# algyan_8th_es.net
KiCad netlist of a schematic drawn in EAGLE
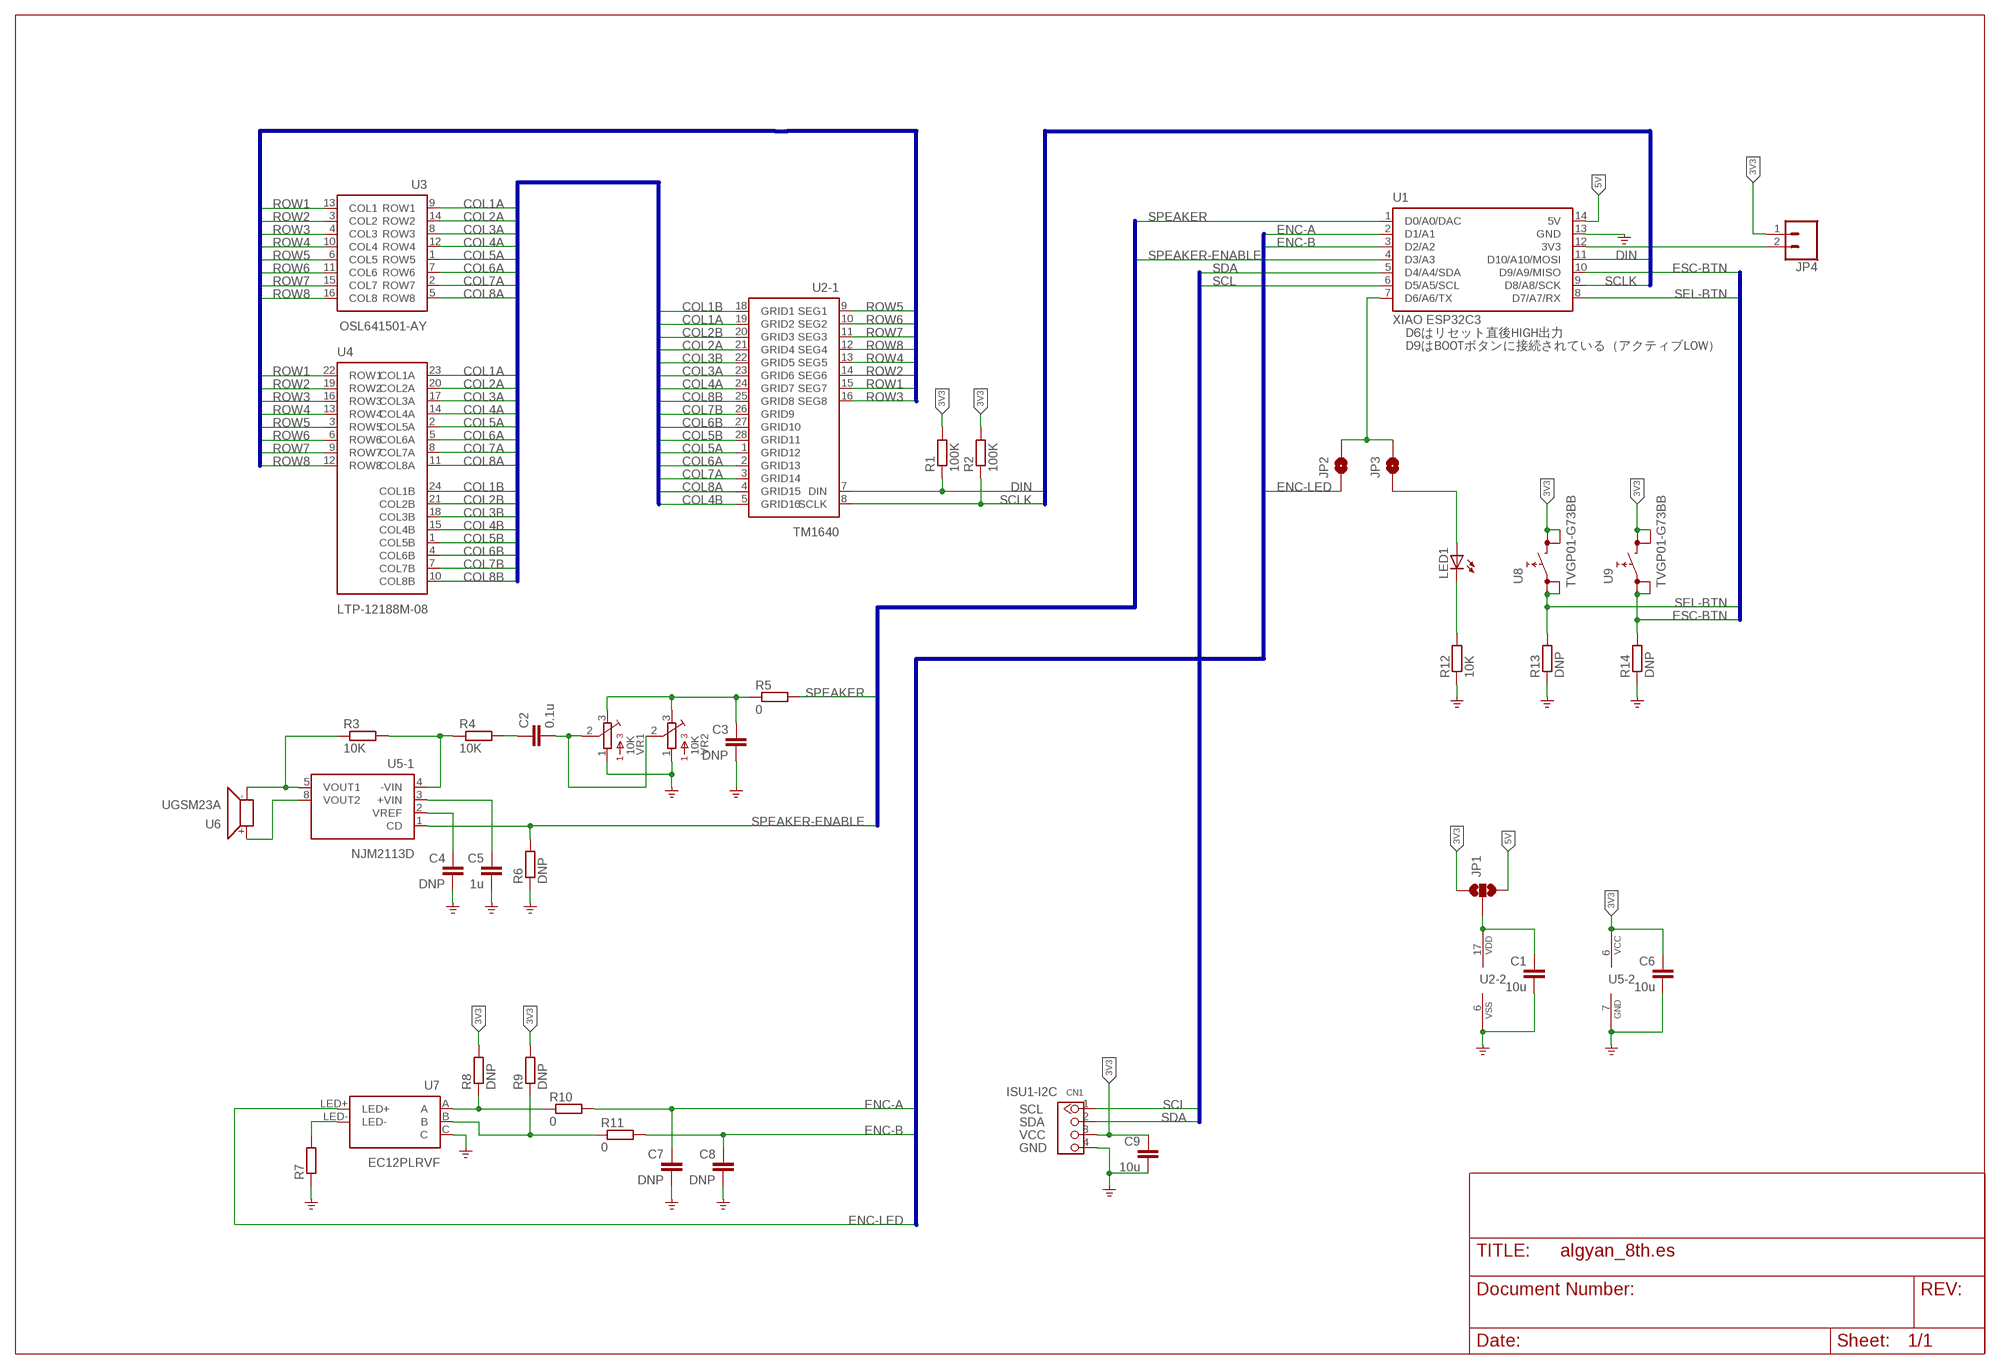
[diagram p0: schematic, sheet 1]

(export (version "E")
  (design (tool "Eeschema 10.0.6"))
  (components
    (comp (ref "C1")
      (value "10u")
      (footprint "eagle-import:C0805")
      (libsource (lib "eagle-import") (part "C-EUC0805"))
    )
    (comp (ref "C2")
      (value "0.1u")
      (footprint "eagle-import:C0603")
      (libsource (lib "eagle-import") (part "C-EUC0603"))
    )
    (comp (ref "C3")
      (value "DNP")
      (footprint "eagle-import:C0805")
      (libsource (lib "eagle-import") (part "C-EUC0805"))
    )
    (comp (ref "C4")
      (value "DNP")
      (footprint "eagle-import:C0805")
      (libsource (lib "eagle-import") (part "C-EUC0805"))
    )
    (comp (ref "C5")
      (value "1u")
      (footprint "eagle-import:C0805")
      (libsource (lib "eagle-import") (part "C-EUC0805"))
    )
    (comp (ref "C6")
      (value "10u")
      (footprint "eagle-import:C0805")
      (libsource (lib "eagle-import") (part "C-EUC0805"))
    )
    (comp (ref "C7")
      (value "DNP")
      (footprint "eagle-import:C0603")
      (libsource (lib "eagle-import") (part "C-EUC0603"))
    )
    (comp (ref "C8")
      (value "DNP")
      (footprint "eagle-import:C0603")
      (libsource (lib "eagle-import") (part "C-EUC0603"))
    )
    (comp (ref "C9")
      (value "10u")
      (footprint "eagle-import:C0805")
      (libsource (lib "eagle-import") (part "C-EUC0805"))
    )
    (comp (ref "CN1")
      (value "4P-2.0")
      (footprint "eagle-import:HW4-2.0")
      (libsource (lib "eagle-import") (part "GROVE-CONNECTOR-DIP(4P-2.0)"))
    )
    (comp (ref "JP1")
      (value "JUMPER-SMT_3_NO_SILK")
      (footprint "eagle-import:SMT-JUMPER_3_NO_SILK")
      (libsource (lib "eagle-import") (part "JUMPER-SMT_3_NO_SILK"))
    )
    (comp (ref "JP2")
      (value "JUMPER-SMT_2_NO_SILK")
      (footprint "eagle-import:SMT-JUMPER_2_NO_SILK")
      (libsource (lib "eagle-import") (part "JUMPER-SMT_2_NO_SILK"))
    )
    (comp (ref "JP3")
      (value "JUMPER-SMT_2_NO_SILK")
      (footprint "eagle-import:SMT-JUMPER_2_NO_SILK")
      (libsource (lib "eagle-import") (part "JUMPER-SMT_2_NO_SILK"))
    )
    (comp (ref "JP4")
      (value "CONN_02")
      (footprint "eagle-import:1X02")
      (libsource (lib "eagle-import") (part "CONN_02"))
    )
    (comp (ref "LED1")
      (value "LED5MM")
      (footprint "eagle-import:LED5MM")
      (libsource (lib "eagle-import") (part "LED5MM"))
    )
    (comp (ref "R1")
      (value "100K")
      (footprint "eagle-import:R0603")
      (libsource (lib "eagle-import") (part "R-EU_R0603"))
    )
    (comp (ref "R2")
      (value "100K")
      (footprint "eagle-import:R0603")
      (libsource (lib "eagle-import") (part "R-EU_R0603"))
    )
    (comp (ref "R3")
      (value "10K")
      (footprint "eagle-import:R0603")
      (libsource (lib "eagle-import") (part "R-EU_R0603"))
    )
    (comp (ref "R4")
      (value "10K")
      (footprint "eagle-import:R0603")
      (libsource (lib "eagle-import") (part "R-EU_R0603"))
    )
    (comp (ref "R5")
      (value "0")
      (footprint "eagle-import:R0603")
      (libsource (lib "eagle-import") (part "R-EU_R0603"))
    )
    (comp (ref "R6")
      (value "DNP")
      (footprint "eagle-import:R0603")
      (libsource (lib "eagle-import") (part "R-EU_R0603"))
    )
    (comp (ref "R7")
      (value "R-EU_R0603")
      (footprint "eagle-import:R0603")
      (libsource (lib "eagle-import") (part "R-EU_R0603"))
    )
    (comp (ref "R8")
      (value "DNP")
      (footprint "eagle-import:R0603")
      (libsource (lib "eagle-import") (part "R-EU_R0603"))
    )
    (comp (ref "R9")
      (value "DNP")
      (footprint "eagle-import:R0603")
      (libsource (lib "eagle-import") (part "R-EU_R0603"))
    )
    (comp (ref "R10")
      (value "0")
      (footprint "eagle-import:R0603")
      (libsource (lib "eagle-import") (part "R-EU_R0603"))
    )
    (comp (ref "R11")
      (value "0")
      (footprint "eagle-import:R0603")
      (libsource (lib "eagle-import") (part "R-EU_R0603"))
    )
    (comp (ref "R12")
      (value "10K")
      (footprint "eagle-import:R0603")
      (libsource (lib "eagle-import") (part "R-EU_R0603"))
    )
    (comp (ref "R13")
      (value "DNP")
      (footprint "eagle-import:R0603")
      (libsource (lib "eagle-import") (part "R-EU_R0603"))
    )
    (comp (ref "R14")
      (value "DNP")
      (footprint "eagle-import:R0603")
      (libsource (lib "eagle-import") (part "R-EU_R0603"))
    )
    (comp (ref "U1")
      (value "XIAO ESP32C3")
      (footprint "eagle-import:SEEEDUINOXIAO")
      (libsource (lib "eagle-import") (part "SEEEDUINOXIAO"))
    )
    (comp (ref "U2")
      (value "TM1640")
      (footprint "eagle-import:TM1640")
      (libsource (lib "eagle-import") (part "TM1640"))
    )
    (comp (ref "U3")
      (value "OSL641501-AY")
      (footprint "eagle-import:OSL641501")
      (libsource (lib "eagle-import") (part "OSL641501-AY"))
    )
    (comp (ref "U4")
      (value "LTP-12188M-08")
      (footprint "eagle-import:LTP-12188M")
      (libsource (lib "eagle-import") (part "LTP-12188M-08"))
    )
    (comp (ref "U5")
      (value "NJM2113D")
      (footprint "eagle-import:DIL08")
      (libsource (lib "eagle-import") (part "NJM2113D"))
    )
    (comp (ref "U6")
      (value "UGSM23A")
      (footprint "eagle-import:UGSM23A")
      (libsource (lib "eagle-import") (part "UGSM23A"))
    )
    (comp (ref "U7")
      (value "EC12PLRVF")
      (footprint "eagle-import:EC12PLRVF")
      (libsource (lib "eagle-import") (part "EC12PLVFR"))
    )
    (comp (ref "U8")
      (value "TVGP01-G73BB")
      (footprint "eagle-import:TVGP01-G73BB")
      (libsource (lib "eagle-import") (part "TVGP01-G73BB"))
    )
    (comp (ref "U9")
      (value "TVGP01-G73BB")
      (footprint "eagle-import:TVGP01-G73BB")
      (libsource (lib "eagle-import") (part "TVGP01-G73BB"))
    )
    (comp (ref "VR1")
      (value "10K")
      (footprint "eagle-import:3386K")
      (libsource (lib "eagle-import") (part "3386-K"))
    )
    (comp (ref "VR2")
      (value "10K")
      (footprint "eagle-import:3386T")
      (libsource (lib "eagle-import") (part "3386-T"))
    )
  )
  (nets
    (net (code "1") (name "/COL1A") (class "Default")
      (node (ref "U2") (pin "19") (pinfunction "GRID2_19") (pintype "output"))
      (node (ref "U3") (pin "9") (pinfunction "ROW1_9") (pintype "input"))
      (node (ref "U4") (pin "23") (pinfunction "COL1A_23") (pintype "input"))
    )
    (net (code "2") (name "/COL1B") (class "Default")
      (node (ref "U2") (pin "18") (pinfunction "GRID1_18") (pintype "output"))
      (node (ref "U4") (pin "24") (pinfunction "COL1B_24") (pintype "input"))
    )
    (net (code "3") (name "/COL2A") (class "Default")
      (node (ref "U2") (pin "21") (pinfunction "GRID4_21") (pintype "output"))
      (node (ref "U3") (pin "14") (pinfunction "ROW2_14") (pintype "input"))
      (node (ref "U4") (pin "20") (pinfunction "COL2A_20") (pintype "input"))
    )
    (net (code "4") (name "/COL2B") (class "Default")
      (node (ref "U2") (pin "20") (pinfunction "GRID3_20") (pintype "output"))
      (node (ref "U4") (pin "21") (pinfunction "COL2B_21") (pintype "input"))
    )
    (net (code "5") (name "/COL3A") (class "Default")
      (node (ref "U2") (pin "23") (pinfunction "GRID6_23") (pintype "output"))
      (node (ref "U3") (pin "8") (pinfunction "ROW3_8") (pintype "input"))
      (node (ref "U4") (pin "17") (pinfunction "COL3A_17") (pintype "input"))
    )
    (net (code "6") (name "/COL3B") (class "Default")
      (node (ref "U2") (pin "22") (pinfunction "GRID5_22") (pintype "output"))
      (node (ref "U4") (pin "18") (pinfunction "COL3B_18") (pintype "input"))
    )
    (net (code "7") (name "/COL4A") (class "Default")
      (node (ref "U2") (pin "24") (pinfunction "GRID7_24") (pintype "output"))
      (node (ref "U3") (pin "12") (pinfunction "ROW4_12") (pintype "input"))
      (node (ref "U4") (pin "14") (pinfunction "COL4A_14") (pintype "input"))
    )
    (net (code "8") (name "/COL4B") (class "Default")
      (node (ref "U2") (pin "5") (pinfunction "GRID16_5") (pintype "output"))
      (node (ref "U4") (pin "15") (pinfunction "COL4B_15") (pintype "input"))
    )
    (net (code "9") (name "/COL5A") (class "Default")
      (node (ref "U2") (pin "1") (pinfunction "GRID12_1") (pintype "output"))
      (node (ref "U3") (pin "1") (pinfunction "ROW5_1") (pintype "input"))
      (node (ref "U4") (pin "2") (pinfunction "COL5A_2") (pintype "input"))
    )
    (net (code "10") (name "/COL5B") (class "Default")
      (node (ref "U2") (pin "28") (pinfunction "GRID11_28") (pintype "output"))
      (node (ref "U4") (pin "1") (pinfunction "COL5B_1") (pintype "input"))
    )
    (net (code "11") (name "/COL6A") (class "Default")
      (node (ref "U2") (pin "2") (pinfunction "GRID13_2") (pintype "output"))
      (node (ref "U3") (pin "7") (pinfunction "ROW6_7") (pintype "input"))
      (node (ref "U4") (pin "5") (pinfunction "COL6A_5") (pintype "input"))
    )
    (net (code "12") (name "/COL6B") (class "Default")
      (node (ref "U2") (pin "27") (pinfunction "GRID10_27") (pintype "output"))
      (node (ref "U4") (pin "4") (pinfunction "COL6B_4") (pintype "input"))
    )
    (net (code "13") (name "/COL7A") (class "Default")
      (node (ref "U2") (pin "3") (pinfunction "GRID14_3") (pintype "output"))
      (node (ref "U3") (pin "2") (pinfunction "ROW7_2") (pintype "input"))
      (node (ref "U4") (pin "8") (pinfunction "COL7A_8") (pintype "input"))
    )
    (net (code "14") (name "/COL7B") (class "Default")
      (node (ref "U2") (pin "26") (pinfunction "GRID9_26") (pintype "output"))
      (node (ref "U4") (pin "7") (pinfunction "COL7B_7") (pintype "input"))
    )
    (net (code "15") (name "/COL8A") (class "Default")
      (node (ref "U2") (pin "4") (pinfunction "GRID15_4") (pintype "output"))
      (node (ref "U3") (pin "5") (pinfunction "ROW8_5") (pintype "input"))
      (node (ref "U4") (pin "11") (pinfunction "COL8A_11") (pintype "input"))
    )
    (net (code "16") (name "/COL8B") (class "Default")
      (node (ref "U2") (pin "25") (pinfunction "GRID8_25") (pintype "output"))
      (node (ref "U4") (pin "10") (pinfunction "COL8B_10") (pintype "input"))
    )
    (net (code "17") (name "/DIN") (class "Default")
      (node (ref "R1") (pin "1") (pinfunction "1_1") (pintype "passive"))
      (node (ref "U1") (pin "11") (pinfunction "D10/A10/MOSI_11") (pintype "bidirectional"))
      (node (ref "U2") (pin "7") (pinfunction "DIN_7") (pintype "output"))
    )
    (net (code "18") (name "/ENC-A") (class "Default")
      (node (ref "C7") (pin "1") (pinfunction "1_1") (pintype "passive"))
      (node (ref "R10") (pin "2") (pinfunction "2_2") (pintype "passive"))
      (node (ref "U1") (pin "2") (pinfunction "D1/A1_2") (pintype "bidirectional"))
    )
    (net (code "19") (name "/ENC-B") (class "Default")
      (node (ref "C8") (pin "1") (pinfunction "1_1") (pintype "passive"))
      (node (ref "R11") (pin "2") (pinfunction "2_2") (pintype "passive"))
      (node (ref "U1") (pin "3") (pinfunction "D2/A2_3") (pintype "bidirectional"))
    )
    (net (code "20") (name "/ENC-LED") (class "Default")
      (node (ref "JP2") (pin "1") (pinfunction "1_1") (pintype "passive"))
      (node (ref "U7") (pin "LED+") (pinfunction "LED+_LED+") (pintype "input"))
    )
    (net (code "21") (name "/ESC-BTN") (class "Default")
      (node (ref "R14") (pin "2") (pinfunction "2_2") (pintype "passive"))
      (node (ref "U1") (pin "10") (pinfunction "D9/A9/MISO_10") (pintype "bidirectional"))
      (node (ref "U9") (pin "1") (pinfunction "0_1") (pintype "passive"))
      (node (ref "U9") (pin "2") (pinfunction "0_2") (pintype "passive"))
    )
    (net (code "22") (name "/ROW1") (class "Default")
      (node (ref "U2") (pin "15") (pinfunction "SEG7_15") (pintype "output"))
      (node (ref "U3") (pin "13") (pinfunction "COL1_13") (pintype "input"))
      (node (ref "U4") (pin "22") (pinfunction "ROW1_22") (pintype "input"))
    )
    (net (code "23") (name "/ROW2") (class "Default")
      (node (ref "U2") (pin "14") (pinfunction "SEG6_14") (pintype "output"))
      (node (ref "U3") (pin "3") (pinfunction "COL2_3") (pintype "input"))
      (node (ref "U4") (pin "19") (pinfunction "ROW2_19") (pintype "input"))
    )
    (net (code "24") (name "/ROW3") (class "Default")
      (node (ref "U2") (pin "16") (pinfunction "SEG8_16") (pintype "output"))
      (node (ref "U3") (pin "4") (pinfunction "COL3_4") (pintype "input"))
      (node (ref "U4") (pin "16") (pinfunction "ROW3_16") (pintype "input"))
    )
    (net (code "25") (name "/ROW4") (class "Default")
      (node (ref "U2") (pin "13") (pinfunction "SEG5_13") (pintype "output"))
      (node (ref "U3") (pin "10") (pinfunction "COL4_10") (pintype "input"))
      (node (ref "U4") (pin "13") (pinfunction "ROW4_13") (pintype "input"))
    )
    (net (code "26") (name "/ROW5") (class "Default")
      (node (ref "U2") (pin "9") (pinfunction "SEG1_9") (pintype "output"))
      (node (ref "U3") (pin "6") (pinfunction "COL5_6") (pintype "input"))
      (node (ref "U4") (pin "3") (pinfunction "ROW5_3") (pintype "input"))
    )
    (net (code "27") (name "/ROW6") (class "Default")
      (node (ref "U2") (pin "10") (pinfunction "SEG2_10") (pintype "output"))
      (node (ref "U3") (pin "11") (pinfunction "COL6_11") (pintype "input"))
      (node (ref "U4") (pin "6") (pinfunction "ROW6_6") (pintype "input"))
    )
    (net (code "28") (name "/ROW7") (class "Default")
      (node (ref "U2") (pin "11") (pinfunction "SEG3_11") (pintype "output"))
      (node (ref "U3") (pin "15") (pinfunction "COL7_15") (pintype "input"))
      (node (ref "U4") (pin "9") (pinfunction "ROW7_9") (pintype "input"))
    )
    (net (code "29") (name "/ROW8") (class "Default")
      (node (ref "U2") (pin "12") (pinfunction "SEG4_12") (pintype "output"))
      (node (ref "U3") (pin "16") (pinfunction "COL8_16") (pintype "input"))
      (node (ref "U4") (pin "12") (pinfunction "ROW8_12") (pintype "input"))
    )
    (net (code "30") (name "/SCL") (class "Default")
      (node (ref "CN1") (pin "1") (pinfunction "1_1") (pintype "bidirectional"))
      (node (ref "U1") (pin "6") (pinfunction "D5/A5/SCL_6") (pintype "bidirectional"))
    )
    (net (code "31") (name "/SCLK") (class "Default")
      (node (ref "R2") (pin "1") (pinfunction "1_1") (pintype "passive"))
      (node (ref "U1") (pin "9") (pinfunction "D8/A8/SCK_9") (pintype "bidirectional"))
      (node (ref "U2") (pin "8") (pinfunction "SCLK_8") (pintype "output"))
    )
    (net (code "32") (name "/SDA") (class "Default")
      (node (ref "CN1") (pin "2") (pinfunction "2_2") (pintype "bidirectional"))
      (node (ref "U1") (pin "5") (pinfunction "D4/A4/SDA_5") (pintype "bidirectional"))
    )
    (net (code "33") (name "/SEL-BTN") (class "Default")
      (node (ref "R13") (pin "2") (pinfunction "2_2") (pintype "passive"))
      (node (ref "U1") (pin "8") (pinfunction "D7/A7/RX_8") (pintype "bidirectional"))
      (node (ref "U8") (pin "1") (pinfunction "0_1") (pintype "passive"))
      (node (ref "U8") (pin "2") (pinfunction "0_2") (pintype "passive"))
    )
    (net (code "34") (name "/SPEAKER") (class "Default")
      (node (ref "R5") (pin "2") (pinfunction "2_2") (pintype "passive"))
      (node (ref "U1") (pin "1") (pinfunction "D0/A0/DAC_1") (pintype "bidirectional"))
    )
    (net (code "35") (name "/SPEAKER-ENABLE") (class "Default")
      (node (ref "R6") (pin "2") (pinfunction "2_2") (pintype "passive"))
      (node (ref "U1") (pin "4") (pinfunction "D3/A3_4") (pintype "input"))
      (node (ref "U5") (pin "1") (pinfunction "CD_1") (pintype "input"))
    )
    (net (code "36") (name "3V3") (class "Default")
      (node (ref "C6") (pin "1") (pinfunction "1_1") (pintype "passive"))
      (node (ref "C9") (pin "1") (pinfunction "1_1") (pintype "passive"))
      (node (ref "CN1") (pin "3") (pinfunction "3_3") (pintype "bidirectional"))
      (node (ref "JP1") (pin "1") (pinfunction "1_1") (pintype "passive"))
      (node (ref "JP4") (pin "1") (pinfunction "1_1") (pintype "passive"))
      (node (ref "R1") (pin "2") (pinfunction "2_2") (pintype "passive"))
      (node (ref "R2") (pin "2") (pinfunction "2_2") (pintype "passive"))
      (node (ref "R8") (pin "2") (pinfunction "2_2") (pintype "passive"))
      (node (ref "R9") (pin "2") (pinfunction "2_2") (pintype "passive"))
      (node (ref "U5") (pin "6") (pinfunction "VCC_6") (pintype "power_in"))
      (node (ref "U8") (pin "3") (pinfunction "1_3") (pintype "passive"))
      (node (ref "U8") (pin "4") (pinfunction "1_4") (pintype "passive"))
      (node (ref "U9") (pin "3") (pinfunction "1_3") (pintype "passive"))
      (node (ref "U9") (pin "4") (pinfunction "1_4") (pintype "passive"))
    )
    (net (code "37") (name "5V") (class "Default")
      (node (ref "JP1") (pin "3") (pinfunction "3_3") (pintype "passive"))
      (node (ref "U1") (pin "14") (pinfunction "5V_14") (pintype "bidirectional"))
    )
    (net (code "38") (name "GND_POWER") (class "Default")
      (node (ref "C1") (pin "2") (pinfunction "2_2") (pintype "passive"))
      (node (ref "C3") (pin "2") (pinfunction "2_2") (pintype "passive"))
      (node (ref "C4") (pin "2") (pinfunction "2_2") (pintype "passive"))
      (node (ref "C5") (pin "2") (pinfunction "2_2") (pintype "passive"))
      (node (ref "C6") (pin "2") (pinfunction "2_2") (pintype "passive"))
      (node (ref "C7") (pin "2") (pinfunction "2_2") (pintype "passive"))
      (node (ref "C8") (pin "2") (pinfunction "2_2") (pintype "passive"))
      (node (ref "C9") (pin "2") (pinfunction "2_2") (pintype "passive"))
      (node (ref "CN1") (pin "4") (pinfunction "4_4") (pintype "bidirectional"))
      (node (ref "R12") (pin "1") (pinfunction "1_1") (pintype "passive"))
      (node (ref "R13") (pin "1") (pinfunction "1_1") (pintype "passive"))
      (node (ref "R14") (pin "1") (pinfunction "1_1") (pintype "passive"))
      (node (ref "R6") (pin "1") (pinfunction "1_1") (pintype "passive"))
      (node (ref "R7") (pin "1") (pinfunction "1_1") (pintype "passive"))
      (node (ref "U1") (pin "13") (pinfunction "GND_13") (pintype "bidirectional"))
      (node (ref "U2") (pin "6") (pinfunction "VSS_6") (pintype "power_in"))
      (node (ref "U5") (pin "7") (pinfunction "GND_7") (pintype "power_in"))
      (node (ref "U7") (pin "C") (pinfunction "C_C") (pintype "passive"))
      (node (ref "VR1") (pin "1") (pinfunction "1_1") (pintype "passive"))
      (node (ref "VR2") (pin "1") (pinfunction "1_1") (pintype "passive"))
    )
    (net (code "39") (name "Net-(C2-Pad1)") (class "Default")
      (node (ref "C2") (pin "1") (pinfunction "1_1") (pintype "passive"))
      (node (ref "R4") (pin "2") (pinfunction "2_2") (pintype "passive"))
    )
    (net (code "40") (name "Net-(C2-Pad2)") (class "Default")
      (node (ref "C2") (pin "2") (pinfunction "2_2") (pintype "passive"))
      (node (ref "VR1") (pin "2") (pinfunction "2_2") (pintype "passive"))
      (node (ref "VR2") (pin "2") (pinfunction "2_2") (pintype "passive"))
    )
    (net (code "41") (name "Net-(C3-Pad1)") (class "Default")
      (node (ref "C3") (pin "1") (pinfunction "1_1") (pintype "passive"))
      (node (ref "R5") (pin "1") (pinfunction "1_1") (pintype "passive"))
      (node (ref "VR1") (pin "3") (pinfunction "3_3") (pintype "passive"))
      (node (ref "VR2") (pin "3") (pinfunction "3_3") (pintype "passive"))
    )
    (net (code "42") (name "Net-(JP3-Pad1)") (class "Default")
      (node (ref "JP3") (pin "1") (pinfunction "1_1") (pintype "passive"))
      (node (ref "LED1") (pin "A") (pinfunction "A_A") (pintype "passive"))
    )
    (net (code "43") (name "Net-(LED1-C)") (class "Default")
      (node (ref "LED1") (pin "K") (pinfunction "C_K") (pintype "passive"))
      (node (ref "R12") (pin "2") (pinfunction "2_2") (pintype "passive"))
    )
    (net (code "44") (name "Net-(R7-Pad2)") (class "Default")
      (node (ref "R7") (pin "2") (pinfunction "2_2") (pintype "passive"))
      (node (ref "U7") (pin "LED-") (pinfunction "LED-_LED-") (pintype "input"))
    )
    (net (code "45") (name "Net-(R10-Pad1)") (class "Default")
      (node (ref "R10") (pin "1") (pinfunction "1_1") (pintype "passive"))
      (node (ref "R8") (pin "1") (pinfunction "1_1") (pintype "passive"))
      (node (ref "U7") (pin "A") (pinfunction "A_A") (pintype "passive"))
    )
    (net (code "46") (name "Net-(R11-Pad1)") (class "Default")
      (node (ref "R11") (pin "1") (pinfunction "1_1") (pintype "passive"))
      (node (ref "R9") (pin "1") (pinfunction "1_1") (pintype "passive"))
      (node (ref "U7") (pin "B") (pinfunction "B_B") (pintype "passive"))
    )
    (net (code "47") (name "Net-(U1-3V3)") (class "Default")
      (node (ref "JP4") (pin "2") (pinfunction "2_2") (pintype "passive"))
      (node (ref "U1") (pin "12") (pinfunction "3V3_12") (pintype "bidirectional"))
    )
    (net (code "48") (name "Net-(U1-D6{slash}A6{slash}TX)") (class "Default")
      (node (ref "JP2") (pin "2") (pinfunction "2_2") (pintype "passive"))
      (node (ref "JP3") (pin "2") (pinfunction "2_2") (pintype "passive"))
      (node (ref "U1") (pin "7") (pinfunction "D6/A6/TX_7") (pintype "bidirectional"))
    )
    (net (code "49") (name "Net-(U2B-VDD)") (class "Default")
      (node (ref "C1") (pin "1") (pinfunction "1_1") (pintype "passive"))
      (node (ref "JP1") (pin "2") (pinfunction "2_2") (pintype "passive"))
      (node (ref "U2") (pin "17") (pinfunction "VDD_17") (pintype "power_in"))
    )
    (net (code "50") (name "Net-(U5A-+VIN)") (class "Default")
      (node (ref "C5") (pin "1") (pinfunction "1_1") (pintype "passive"))
      (node (ref "U5") (pin "3") (pinfunction "+VIN_3") (pintype "input"))
    )
    (net (code "51") (name "Net-(U5A--VIN)") (class "Default")
      (node (ref "R3") (pin "2") (pinfunction "2_2") (pintype "passive"))
      (node (ref "R4") (pin "1") (pinfunction "1_1") (pintype "passive"))
      (node (ref "U5") (pin "4") (pinfunction "-VIN_4") (pintype "input"))
    )
    (net (code "52") (name "Net-(U5A-VOUT1)") (class "Default")
      (node (ref "R3") (pin "1") (pinfunction "1_1") (pintype "passive"))
      (node (ref "U5") (pin "5") (pinfunction "VOUT1_5") (pintype "output"))
      (node (ref "U6") (pin "-") (pinfunction "2_-") (pintype "passive"))
    )
    (net (code "53") (name "Net-(U5A-VOUT2)") (class "Default")
      (node (ref "U5") (pin "8") (pinfunction "VOUT2_8") (pintype "output"))
      (node (ref "U6") (pin "+") (pinfunction "1_+") (pintype "passive"))
    )
    (net (code "54") (name "Net-(U5A-VREF)") (class "Default")
      (node (ref "C4") (pin "1") (pinfunction "1_1") (pintype "passive"))
      (node (ref "U5") (pin "2") (pinfunction "VREF_2") (pintype "input"))
    )
  )
)
